# EasyEDAProDoc_P2303U1-electronicbox_2024.net
KiCad netlist of a schematic drawn in EasyEDA Pro
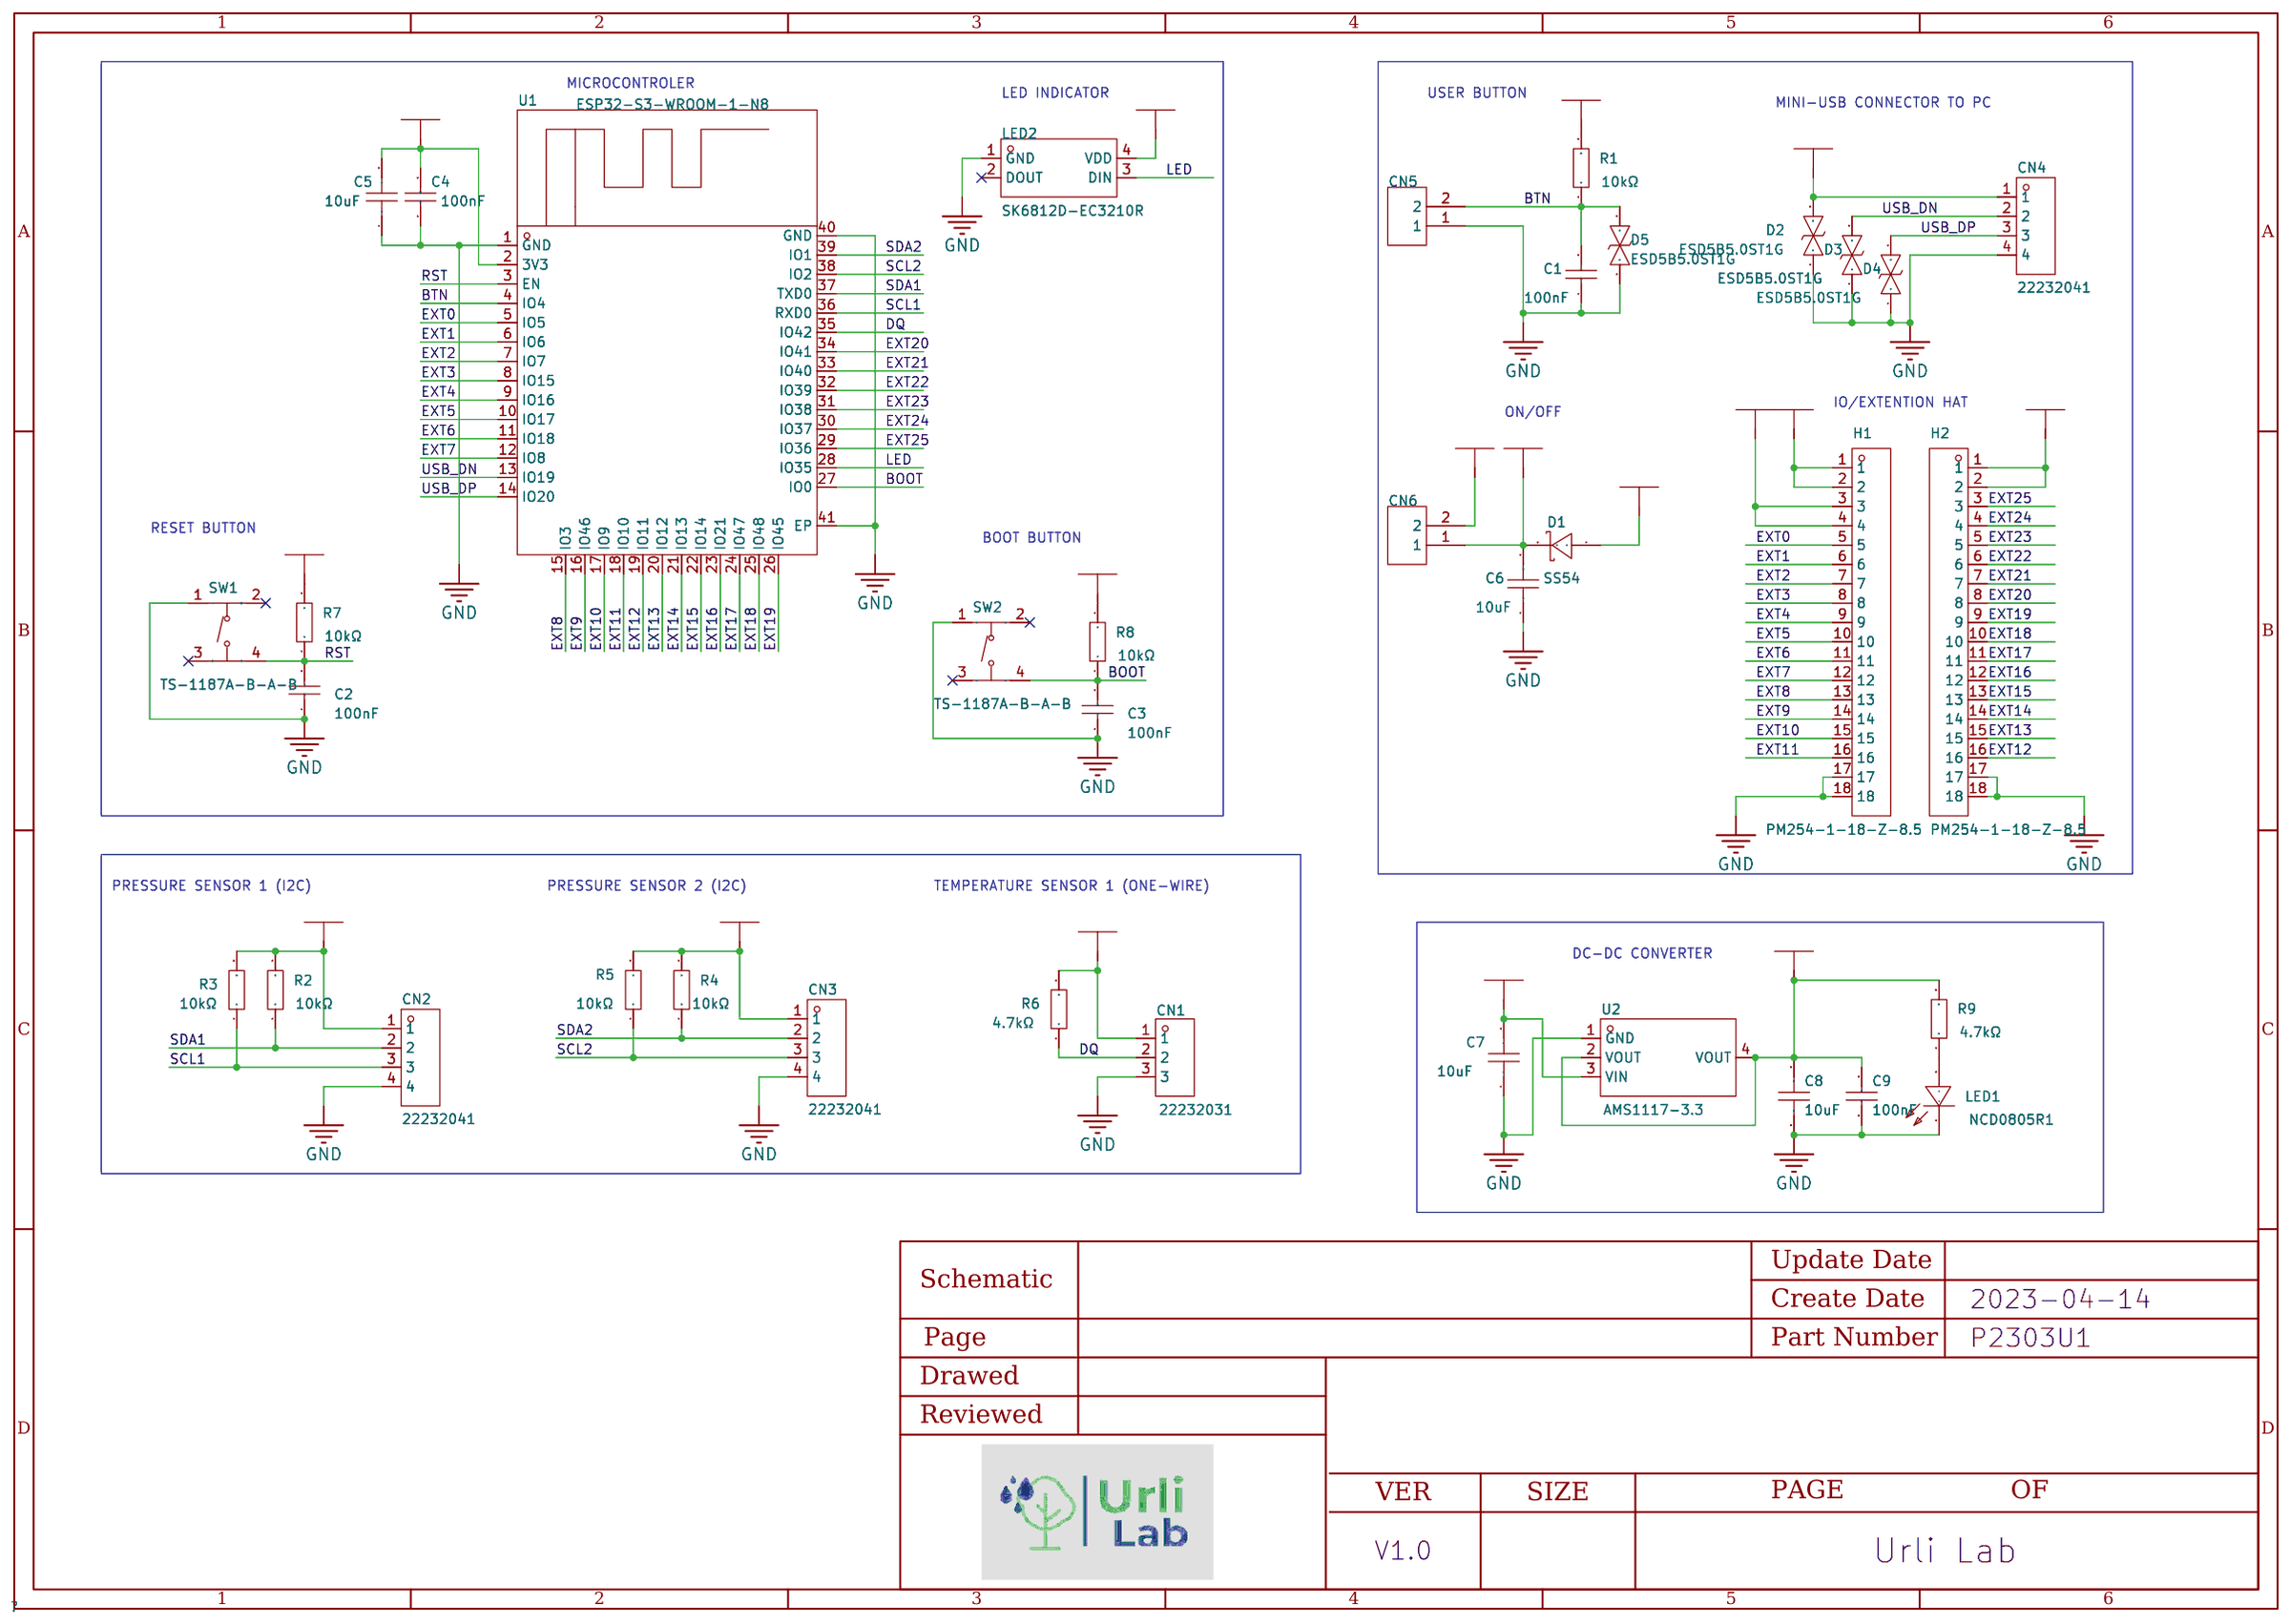
[diagram p0: schematic sheet]

(export (version "E")
  (design (tool "Eeschema 10.0.6"))
  (components
    (comp (ref "C1")
      (value "100nF")
      (footprint "easyedapro:C0805")
      (fields
        (field (name "Manufacturer Part") "CC0805KRX7R9BB104")
        (field (name "Manufacturer") "YAGEO(国巨)")
      )
      (libsource (lib "easyedapro") (part "CC0805KRX7R9BB104"))
    )
    (comp (ref "C2")
      (value "100nF")
      (footprint "easyedapro:C0805")
      (fields
        (field (name "Manufacturer Part") "CC0805KRX7R9BB104")
        (field (name "Manufacturer") "YAGEO(国巨)")
      )
      (libsource (lib "easyedapro") (part "CC0805KRX7R9BB104"))
    )
    (comp (ref "C3")
      (value "100nF")
      (footprint "easyedapro:C0805")
      (fields
        (field (name "Manufacturer Part") "CC0805KRX7R9BB104")
        (field (name "Manufacturer") "YAGEO(国巨)")
      )
      (libsource (lib "easyedapro") (part "CC0805KRX7R9BB104"))
    )
    (comp (ref "C4")
      (value "100nF")
      (footprint "easyedapro:C0805")
      (fields
        (field (name "Manufacturer Part") "CC0805KRX7R9BB104")
        (field (name "Manufacturer") "YAGEO(国巨)")
      )
      (libsource (lib "easyedapro") (part "CC0805KRX7R9BB104"))
    )
    (comp (ref "C5")
      (value "10uF")
      (footprint "easyedapro:C0805")
      (fields
        (field (name "Manufacturer Part") "GRM21BR61H106KE43L")
        (field (name "Manufacturer") "muRata(村田)")
      )
      (libsource (lib "easyedapro") (part "GRM21BR61H106KE43L"))
    )
    (comp (ref "C6")
      (value "10uF")
      (footprint "easyedapro:C0805")
      (fields
        (field (name "Manufacturer Part") "GRM21BR61H106KE43L")
        (field (name "Manufacturer") "muRata(村田)")
      )
      (libsource (lib "easyedapro") (part "GRM21BR61H106KE43L"))
    )
    (comp (ref "C7")
      (value "10uF")
      (footprint "easyedapro:C0805")
      (fields
        (field (name "Manufacturer Part") "GRM21BR61H106KE43L")
        (field (name "Manufacturer") "muRata(村田)")
      )
      (libsource (lib "easyedapro") (part "GRM21BR61H106KE43L"))
    )
    (comp (ref "C8")
      (value "10uF")
      (footprint "easyedapro:C0805")
      (fields
        (field (name "Manufacturer Part") "GRM21BR61H106KE43L")
        (field (name "Manufacturer") "muRata(村田)")
      )
      (libsource (lib "easyedapro") (part "GRM21BR61H106KE43L"))
    )
    (comp (ref "C9")
      (value "100nF")
      (footprint "easyedapro:C0805")
      (fields
        (field (name "Manufacturer Part") "CC0805KRX7R9BB104")
        (field (name "Manufacturer") "YAGEO(国巨)")
      )
      (libsource (lib "easyedapro") (part "CC0805KRX7R9BB104"))
    )
    (comp (ref "CN1")
      (value "22232031")
      (footprint "easyedapro:CONN-TH_3P-P2.54_22-23-2031")
      (fields (field (name "Manufacturer") "MOLEX"))
      (libsource (lib "easyedapro") (part "22-23-2031"))
    )
    (comp (ref "CN2")
      (value "22232041")
      (footprint "easyedapro:CONN-TH_4P-P2.54_22232041")
      (fields (field (name "Manufacturer") "MOLEX"))
      (libsource (lib "easyedapro") (part "22232041"))
    )
    (comp (ref "CN3")
      (value "22232041")
      (footprint "easyedapro:CONN-TH_4P-P2.54_22232041")
      (fields (field (name "Manufacturer") "MOLEX"))
      (libsource (lib "easyedapro") (part "22232041"))
    )
    (comp (ref "CN4")
      (value "22232041")
      (footprint "easyedapro:CONN-TH_4P-P2.54_22232041")
      (fields (field (name "Manufacturer") "MOLEX"))
      (libsource (lib "easyedapro") (part "22232041"))
    )
    (comp (ref "CN5")
      (value "22-23-2021")
      (fields (field (name "Manufacturer Part") "22232021") (field (name "Manufacturer") "MOLEX"))
      (libsource (lib "easyedapro") (part "0022232021"))
    )
    (comp (ref "CN6")
      (value "22-23-2021")
      (fields (field (name "Manufacturer Part") "22232021") (field (name "Manufacturer") "MOLEX"))
      (libsource (lib "easyedapro") (part "0022232021"))
    )
    (comp (ref "D1")
      (value "SS54")
      (footprint "easyedapro:SMA_L4.4-W2.8-LS5.4-R-RD")
      (description "Reverse Voltage (Vr):40V Average Rectified Current (Io):5A Forward Voltage (Vf@If):550mV@5A")
      (fields (field (name "Manufacturer") "MDD"))
      (libsource (lib "easyedapro") (part "SS54_C22452"))
    )
    (comp (ref "D2")
      (value "ESD5B5.0ST1G")
      (footprint "easyedapro:SOD-523_L1.2-W0.8-LS1.6-BI")
      (fields (field (name "Manufacturer") "onsemi(安森美)"))
      (libsource (lib "easyedapro") (part "ESD5B5.0ST1G"))
    )
    (comp (ref "D3")
      (value "ESD5B5.0ST1G")
      (footprint "easyedapro:SOD-523_L1.2-W0.8-LS1.6-BI")
      (fields (field (name "Manufacturer") "onsemi(安森美)"))
      (libsource (lib "easyedapro") (part "ESD5B5.0ST1G"))
    )
    (comp (ref "D4")
      (value "ESD5B5.0ST1G")
      (footprint "easyedapro:SOD-523_L1.2-W0.8-LS1.6-BI")
      (fields (field (name "Manufacturer") "onsemi(安森美)"))
      (libsource (lib "easyedapro") (part "ESD5B5.0ST1G"))
    )
    (comp (ref "D5")
      (value "ESD5B5.0ST1G")
      (footprint "easyedapro:SOD-523_L1.2-W0.8-LS1.6-BI")
      (fields (field (name "Manufacturer") "onsemi(安森美)"))
      (libsource (lib "easyedapro") (part "ESD5B5.0ST1G"))
    )
    (comp (ref "H1")
      (value "PM254-1-18-Z-8.5")
      (footprint "easyedapro:HDR-TH_18P-P2.54-V-F")
      (fields (field (name "Manufacturer") "HCTL(华灿天禄)"))
      (libsource (lib "easyedapro") (part "PM254-1-18-Z-8.5"))
    )
    (comp (ref "H2")
      (value "PM254-1-18-Z-8.5")
      (footprint "easyedapro:HDR-TH_18P-P2.54-V-F")
      (fields (field (name "Manufacturer") "HCTL(华灿天禄)"))
      (libsource (lib "easyedapro") (part "PM254-1-18-Z-8.5"))
    )
    (comp (ref "LED1")
      (value "NCD0805R1")
      (footprint "easyedapro:LED0805-RD_RED")
      (description "Emitted Color:红灯")
      (fields (field (name "Manufacturer") "国星光电"))
      (libsource (lib "easyedapro") (part "FC-2012HRK-620D"))
    )
    (comp (ref "LED2")
      (value "SK6812D-EC3210R")
      (footprint "easyedapro:LED-SMD_4P_SK6812D-EC3210R")
      (fields (field (name "Manufacturer") "欧思科光电"))
      (libsource (lib "easyedapro") (part "SK6812D-EC3210R"))
    )
    (comp (ref "R1")
      (value "10kΩ")
      (footprint "easyedapro:R0805")
      (fields
        (field (name "Manufacturer Part") "0805W8F1002T5E")
        (field (name "Manufacturer") "UNI-ROYAL(厚声)")
      )
      (libsource (lib "easyedapro") (part "0805W8F1002T5E"))
    )
    (comp (ref "R2")
      (value "10kΩ")
      (footprint "easyedapro:R0805")
      (fields
        (field (name "Manufacturer Part") "0805W8F1002T5E")
        (field (name "Manufacturer") "UNI-ROYAL(厚声)")
      )
      (libsource (lib "easyedapro") (part "0805W8F1002T5E"))
    )
    (comp (ref "R3")
      (value "10kΩ")
      (footprint "easyedapro:R0805")
      (fields
        (field (name "Manufacturer Part") "0805W8F1002T5E")
        (field (name "Manufacturer") "UNI-ROYAL(厚声)")
      )
      (libsource (lib "easyedapro") (part "0805W8F1002T5E"))
    )
    (comp (ref "R4")
      (value "10kΩ")
      (footprint "easyedapro:R0805")
      (fields
        (field (name "Manufacturer Part") "0805W8F1002T5E")
        (field (name "Manufacturer") "UNI-ROYAL(厚声)")
      )
      (libsource (lib "easyedapro") (part "0805W8F1002T5E"))
    )
    (comp (ref "R5")
      (value "10kΩ")
      (footprint "easyedapro:R0805")
      (fields
        (field (name "Manufacturer Part") "0805W8F1002T5E")
        (field (name "Manufacturer") "UNI-ROYAL(厚声)")
      )
      (libsource (lib "easyedapro") (part "0805W8F1002T5E"))
    )
    (comp (ref "R6")
      (value "4.7kΩ")
      (footprint "easyedapro:R0805")
      (fields
        (field (name "Manufacturer Part") "0805W8F4701T5E")
        (field (name "Manufacturer") "UNI-ROYAL(厚声)")
      )
      (libsource (lib "easyedapro") (part "0805W8F4701T5E"))
    )
    (comp (ref "R7")
      (value "10kΩ")
      (footprint "easyedapro:R0805")
      (fields
        (field (name "Manufacturer Part") "0805W8F1002T5E")
        (field (name "Manufacturer") "UNI-ROYAL(厚声)")
      )
      (libsource (lib "easyedapro") (part "0805W8F1002T5E"))
    )
    (comp (ref "R8")
      (value "10kΩ")
      (footprint "easyedapro:R0805")
      (fields
        (field (name "Manufacturer Part") "0805W8F1002T5E")
        (field (name "Manufacturer") "UNI-ROYAL(厚声)")
      )
      (libsource (lib "easyedapro") (part "0805W8F1002T5E"))
    )
    (comp (ref "R9")
      (value "4.7kΩ")
      (footprint "easyedapro:R0805")
      (fields
        (field (name "Manufacturer Part") "0805W8F4701T5E")
        (field (name "Manufacturer") "UNI-ROYAL(厚声)")
      )
      (libsource (lib "easyedapro") (part "0805W8F4701T5E"))
    )
    (comp (ref "SW1")
      (value "TS-1187A-B-A-B")
      (footprint "easyedapro:SW-SMD_4P-L5.1-W5.1-P3.70-LS6.5-TL-2")
      (fields (field (name "Manufacturer") "XKB Connectivity(中国星坤)"))
      (libsource (lib "easyedapro") (part "TS-1187A-B-A-B"))
    )
    (comp (ref "SW2")
      (value "TS-1187A-B-A-B")
      (footprint "easyedapro:SW-SMD_4P-L5.1-W5.1-P3.70-LS6.5-TL-2")
      (fields (field (name "Manufacturer") "XKB Connectivity(中国星坤)"))
      (libsource (lib "easyedapro") (part "TS-1187A-B-A-B"))
    )
    (comp (ref "U1")
      (value "ESP32-S3-WROOM-1-N8")
      (footprint "easyedapro:WIFIM-SMD_ESP32-S3-WROOM-1-N8")
      (fields (field (name "Manufacturer") "ESPRESSIF(乐鑫)"))
      (libsource (lib "easyedapro") (part "ESP32-S3-WROOM-1-N8"))
    )
    (comp (ref "U2")
      (value "AMS1117-3.3")
      (footprint "easyedapro:SOT-223-3_L6.5-W3.4-P2.30-LS7.0-BR")
      (fields (field (name "Manufacturer") "AMS"))
      (libsource (lib "easyedapro") (part "AMS1117-3.3"))
    )
  )
  (nets
    (net (code "1") (name "/BOOT") (class "Default")
      (node (ref "C3") (pin "2") (pinfunction "2_2") (pintype "input"))
      (node (ref "R8") (pin "1") (pinfunction "1_1") (pintype "input"))
      (node (ref "SW2") (pin "4") (pinfunction "D_4") (pintype "input"))
      (node (ref "U1") (pin "27") (pinfunction "IO0_27") (pintype "input"))
    )
    (net (code "2") (name "/BTN") (class "Default")
      (node (ref "C1") (pin "2") (pinfunction "2_2") (pintype "input"))
      (node (ref "CN5") (pin "2") (pinfunction "2_2") (pintype "input"))
      (node (ref "D5") (pin "2") (pinfunction "2_2") (pintype "input"))
      (node (ref "R1") (pin "1") (pinfunction "1_1") (pintype "input"))
      (node (ref "U1") (pin "4") (pinfunction "IO4_4") (pintype "input"))
    )
    (net (code "3") (name "/DQ") (class "Default")
      (node (ref "CN1") (pin "2") (pinfunction "2_2") (pintype "input"))
      (node (ref "R6") (pin "1") (pinfunction "1_1") (pintype "input"))
      (node (ref "U1") (pin "35") (pinfunction "IO42_35") (pintype "input"))
    )
    (net (code "4") (name "/EXT0") (class "Default")
      (node (ref "H1") (pin "5") (pinfunction "5_5") (pintype "input"))
      (node (ref "U1") (pin "5") (pinfunction "IO5_5") (pintype "input"))
    )
    (net (code "5") (name "/EXT1") (class "Default")
      (node (ref "H1") (pin "6") (pinfunction "6_6") (pintype "input"))
      (node (ref "U1") (pin "6") (pinfunction "IO6_6") (pintype "input"))
    )
    (net (code "6") (name "/EXT2") (class "Default")
      (node (ref "H1") (pin "7") (pinfunction "7_7") (pintype "input"))
      (node (ref "U1") (pin "7") (pinfunction "IO7_7") (pintype "input"))
    )
    (net (code "7") (name "/EXT3") (class "Default")
      (node (ref "H1") (pin "8") (pinfunction "8_8") (pintype "input"))
      (node (ref "U1") (pin "8") (pinfunction "IO15_8") (pintype "input"))
    )
    (net (code "8") (name "/EXT4") (class "Default")
      (node (ref "H1") (pin "9") (pinfunction "9_9") (pintype "input"))
      (node (ref "U1") (pin "9") (pinfunction "IO16_9") (pintype "input"))
    )
    (net (code "9") (name "/EXT5") (class "Default")
      (node (ref "H1") (pin "10") (pinfunction "10_10") (pintype "input"))
      (node (ref "U1") (pin "10") (pinfunction "IO17_10") (pintype "input"))
    )
    (net (code "10") (name "/EXT6") (class "Default")
      (node (ref "H1") (pin "11") (pinfunction "11_11") (pintype "input"))
      (node (ref "U1") (pin "11") (pinfunction "IO18_11") (pintype "input"))
    )
    (net (code "11") (name "/EXT7") (class "Default")
      (node (ref "H1") (pin "12") (pinfunction "12_12") (pintype "input"))
      (node (ref "U1") (pin "12") (pinfunction "IO8_12") (pintype "input"))
    )
    (net (code "12") (name "/EXT8") (class "Default")
      (node (ref "H1") (pin "13") (pinfunction "13_13") (pintype "input"))
      (node (ref "U1") (pin "15") (pinfunction "IO3_15") (pintype "input"))
    )
    (net (code "13") (name "/EXT9") (class "Default")
      (node (ref "H1") (pin "14") (pinfunction "14_14") (pintype "input"))
      (node (ref "U1") (pin "16") (pinfunction "IO46_16") (pintype "input"))
    )
    (net (code "14") (name "/EXT10") (class "Default")
      (node (ref "H1") (pin "15") (pinfunction "15_15") (pintype "input"))
      (node (ref "U1") (pin "17") (pinfunction "IO9_17") (pintype "input"))
    )
    (net (code "15") (name "/EXT11") (class "Default")
      (node (ref "H1") (pin "16") (pinfunction "16_16") (pintype "input"))
      (node (ref "U1") (pin "18") (pinfunction "IO10_18") (pintype "input"))
    )
    (net (code "16") (name "/EXT12") (class "Default")
      (node (ref "H2") (pin "16") (pinfunction "16_16") (pintype "input"))
      (node (ref "U1") (pin "19") (pinfunction "IO11_19") (pintype "input"))
    )
    (net (code "17") (name "/EXT13") (class "Default")
      (node (ref "H2") (pin "15") (pinfunction "15_15") (pintype "input"))
      (node (ref "U1") (pin "20") (pinfunction "IO12_20") (pintype "input"))
    )
    (net (code "18") (name "/EXT14") (class "Default")
      (node (ref "H2") (pin "14") (pinfunction "14_14") (pintype "input"))
      (node (ref "U1") (pin "21") (pinfunction "IO13_21") (pintype "input"))
    )
    (net (code "19") (name "/EXT15") (class "Default")
      (node (ref "H2") (pin "13") (pinfunction "13_13") (pintype "input"))
      (node (ref "U1") (pin "22") (pinfunction "IO14_22") (pintype "input"))
    )
    (net (code "20") (name "/EXT16") (class "Default")
      (node (ref "H2") (pin "12") (pinfunction "12_12") (pintype "input"))
      (node (ref "U1") (pin "23") (pinfunction "IO21_23") (pintype "input"))
    )
    (net (code "21") (name "/EXT17") (class "Default")
      (node (ref "H2") (pin "11") (pinfunction "11_11") (pintype "input"))
      (node (ref "U1") (pin "24") (pinfunction "IO47_24") (pintype "input"))
    )
    (net (code "22") (name "/EXT18") (class "Default")
      (node (ref "H2") (pin "10") (pinfunction "10_10") (pintype "input"))
      (node (ref "U1") (pin "25") (pinfunction "IO48_25") (pintype "input"))
    )
    (net (code "23") (name "/EXT19") (class "Default")
      (node (ref "H2") (pin "9") (pinfunction "9_9") (pintype "input"))
      (node (ref "U1") (pin "26") (pinfunction "IO45_26") (pintype "input"))
    )
    (net (code "24") (name "/EXT20") (class "Default")
      (node (ref "H2") (pin "8") (pinfunction "8_8") (pintype "input"))
      (node (ref "U1") (pin "34") (pinfunction "IO41_34") (pintype "input"))
    )
    (net (code "25") (name "/EXT21") (class "Default")
      (node (ref "H2") (pin "7") (pinfunction "7_7") (pintype "input"))
      (node (ref "U1") (pin "33") (pinfunction "IO40_33") (pintype "input"))
    )
    (net (code "26") (name "/EXT22") (class "Default")
      (node (ref "H2") (pin "6") (pinfunction "6_6") (pintype "input"))
      (node (ref "U1") (pin "32") (pinfunction "IO39_32") (pintype "input"))
    )
    (net (code "27") (name "/EXT23") (class "Default")
      (node (ref "H2") (pin "5") (pinfunction "5_5") (pintype "input"))
      (node (ref "U1") (pin "31") (pinfunction "IO38_31") (pintype "input"))
    )
    (net (code "28") (name "/EXT24") (class "Default")
      (node (ref "H2") (pin "4") (pinfunction "4_4") (pintype "input"))
      (node (ref "U1") (pin "30") (pinfunction "IO37_30") (pintype "input"))
    )
    (net (code "29") (name "/EXT25") (class "Default")
      (node (ref "H2") (pin "3") (pinfunction "3_3") (pintype "input"))
      (node (ref "U1") (pin "29") (pinfunction "IO36_29") (pintype "input"))
    )
    (net (code "30") (name "/LED") (class "Default")
      (node (ref "LED2") (pin "3") (pinfunction "DIN_3") (pintype "input"))
      (node (ref "U1") (pin "28") (pinfunction "IO35_28") (pintype "input"))
    )
    (net (code "31") (name "/RST") (class "Default")
      (node (ref "C2") (pin "2") (pinfunction "2_2") (pintype "input"))
      (node (ref "R7") (pin "1") (pinfunction "1_1") (pintype "input"))
      (node (ref "SW1") (pin "4") (pinfunction "D_4") (pintype "input"))
      (node (ref "U1") (pin "3") (pinfunction "EN_3") (pintype "input"))
    )
    (net (code "32") (name "/SCL1") (class "Default")
      (node (ref "CN2") (pin "3") (pinfunction "3_3") (pintype "input"))
      (node (ref "R3") (pin "1") (pinfunction "1_1") (pintype "input"))
      (node (ref "U1") (pin "36") (pinfunction "RXD0_36") (pintype "input"))
    )
    (net (code "33") (name "/SCL2") (class "Default")
      (node (ref "CN3") (pin "3") (pinfunction "3_3") (pintype "input"))
      (node (ref "R5") (pin "1") (pinfunction "1_1") (pintype "input"))
      (node (ref "U1") (pin "38") (pinfunction "IO2_38") (pintype "input"))
    )
    (net (code "34") (name "/SDA1") (class "Default")
      (node (ref "CN2") (pin "2") (pinfunction "2_2") (pintype "input"))
      (node (ref "R2") (pin "1") (pinfunction "1_1") (pintype "input"))
      (node (ref "U1") (pin "37") (pinfunction "TXD0_37") (pintype "input"))
    )
    (net (code "35") (name "/SDA2") (class "Default")
      (node (ref "CN3") (pin "2") (pinfunction "2_2") (pintype "input"))
      (node (ref "R4") (pin "1") (pinfunction "1_1") (pintype "input"))
      (node (ref "U1") (pin "39") (pinfunction "IO1_39") (pintype "input"))
    )
    (net (code "36") (name "/USB_DN") (class "Default")
      (node (ref "CN4") (pin "2") (pinfunction "2_2") (pintype "input"))
      (node (ref "D3") (pin "2") (pinfunction "2_2") (pintype "input"))
      (node (ref "U1") (pin "13") (pinfunction "IO19_13") (pintype "input"))
    )
    (net (code "37") (name "/USB_DP") (class "Default")
      (node (ref "CN4") (pin "3") (pinfunction "3_3") (pintype "input"))
      (node (ref "D4") (pin "2") (pinfunction "2_2") (pintype "input"))
      (node (ref "U1") (pin "14") (pinfunction "IO20_14") (pintype "input"))
    )
    (net (code "38") (name "3V3") (class "Default")
      (node (ref "C4") (pin "2") (pinfunction "2_2") (pintype "input"))
      (node (ref "C5") (pin "2") (pinfunction "2_2") (pintype "input"))
      (node (ref "C8") (pin "2") (pinfunction "2_2") (pintype "input"))
      (node (ref "C9") (pin "2") (pinfunction "2_2") (pintype "input"))
      (node (ref "CN1") (pin "1") (pinfunction "1_1") (pintype "input"))
      (node (ref "CN2") (pin "1") (pinfunction "1_1") (pintype "input"))
      (node (ref "CN3") (pin "1") (pinfunction "1_1") (pintype "input"))
      (node (ref "H2") (pin "1") (pinfunction "1_1") (pintype "input"))
      (node (ref "H2") (pin "2") (pinfunction "2_2") (pintype "input"))
      (node (ref "LED2") (pin "4") (pinfunction "VDD_4") (pintype "input"))
      (node (ref "R1") (pin "2") (pinfunction "2_2") (pintype "input"))
      (node (ref "R2") (pin "2") (pinfunction "2_2") (pintype "input"))
      (node (ref "R3") (pin "2") (pinfunction "2_2") (pintype "input"))
      (node (ref "R4") (pin "2") (pinfunction "2_2") (pintype "input"))
      (node (ref "R5") (pin "2") (pinfunction "2_2") (pintype "input"))
      (node (ref "R6") (pin "2") (pinfunction "2_2") (pintype "input"))
      (node (ref "R7") (pin "2") (pinfunction "2_2") (pintype "input"))
      (node (ref "R8") (pin "2") (pinfunction "2_2") (pintype "input"))
      (node (ref "R9") (pin "2") (pinfunction "2_2") (pintype "input"))
      (node (ref "U1") (pin "2") (pinfunction "3V3_2") (pintype "input"))
      (node (ref "U2") (pin "2") (pinfunction "VOUT_2") (pintype "input"))
      (node (ref "U2") (pin "4") (pinfunction "VOUT_4") (pintype "input"))
    )
    (net (code "39") (name "GND") (class "Default")
      (node (ref "C1") (pin "1") (pinfunction "1_1") (pintype "input"))
      (node (ref "C2") (pin "1") (pinfunction "1_1") (pintype "input"))
      (node (ref "C3") (pin "1") (pinfunction "1_1") (pintype "input"))
      (node (ref "C4") (pin "1") (pinfunction "1_1") (pintype "input"))
      (node (ref "C5") (pin "1") (pinfunction "1_1") (pintype "input"))
      (node (ref "C6") (pin "1") (pinfunction "1_1") (pintype "input"))
      (node (ref "C7") (pin "1") (pinfunction "1_1") (pintype "input"))
      (node (ref "C8") (pin "1") (pinfunction "1_1") (pintype "input"))
      (node (ref "C9") (pin "1") (pinfunction "1_1") (pintype "input"))
      (node (ref "CN1") (pin "3") (pinfunction "3_3") (pintype "input"))
      (node (ref "CN2") (pin "4") (pinfunction "4_4") (pintype "input"))
      (node (ref "CN3") (pin "4") (pinfunction "4_4") (pintype "input"))
      (node (ref "CN4") (pin "4") (pinfunction "4_4") (pintype "input"))
      (node (ref "CN5") (pin "1") (pinfunction "1_1") (pintype "input"))
      (node (ref "D2") (pin "1") (pinfunction "1_1") (pintype "input"))
      (node (ref "D3") (pin "1") (pinfunction "1_1") (pintype "input"))
      (node (ref "D4") (pin "1") (pinfunction "1_1") (pintype "input"))
      (node (ref "D5") (pin "1") (pinfunction "1_1") (pintype "input"))
      (node (ref "H1") (pin "17") (pinfunction "17_17") (pintype "input"))
      (node (ref "H1") (pin "18") (pinfunction "18_18") (pintype "input"))
      (node (ref "H2") (pin "17") (pinfunction "17_17") (pintype "input"))
      (node (ref "H2") (pin "18") (pinfunction "18_18") (pintype "input"))
      (node (ref "LED1") (pin "1") (pinfunction "-_1") (pintype "input"))
      (node (ref "LED2") (pin "1") (pinfunction "GND_1") (pintype "input"))
      (node (ref "SW1") (pin "1") (pinfunction "A_1") (pintype "input"))
      (node (ref "SW2") (pin "1") (pinfunction "A_1") (pintype "input"))
      (node (ref "U1") (pin "1") (pinfunction "GND_1") (pintype "input"))
      (node (ref "U1") (pin "40") (pinfunction "GND_40") (pintype "input"))
      (node (ref "U1") (pin "41") (pinfunction "EP_41") (pintype "input"))
      (node (ref "U2") (pin "1") (pinfunction "GND_1") (pintype "input"))
    )
    (net (code "40") (name "Net-(LED1-+)") (class "Default")
      (node (ref "LED1") (pin "2") (pinfunction "+_2") (pintype "input"))
      (node (ref "R9") (pin "1") (pinfunction "1_1") (pintype "input"))
    )
    (net (code "41") (name "VBUS") (class "Default")
      (node (ref "CN4") (pin "1") (pinfunction "1_1") (pintype "input"))
      (node (ref "D1") (pin "1") (pinfunction "A_1") (pintype "input"))
      (node (ref "D2") (pin "2") (pinfunction "2_2") (pintype "input"))
    )
    (net (code "42") (name "VCC") (class "Default")
      (node (ref "C7") (pin "2") (pinfunction "2_2") (pintype "input"))
      (node (ref "CN6") (pin "2") (pinfunction "2_2") (pintype "input"))
      (node (ref "H1") (pin "1") (pinfunction "1_1") (pintype "input"))
      (node (ref "H1") (pin "2") (pinfunction "2_2") (pintype "input"))
      (node (ref "U2") (pin "3") (pinfunction "VIN_3") (pintype "input"))
    )
    (net (code "43") (name "VIN") (class "Default")
      (node (ref "C6") (pin "2") (pinfunction "2_2") (pintype "input"))
      (node (ref "CN6") (pin "1") (pinfunction "1_1") (pintype "input"))
      (node (ref "D1") (pin "2") (pinfunction "K_2") (pintype "input"))
      (node (ref "H1") (pin "3") (pinfunction "3_3") (pintype "input"))
      (node (ref "H1") (pin "4") (pinfunction "4_4") (pintype "input"))
    )
    (net (code "44") (name "unconnected-(LED2-DOUT-Pad2)") (class "Default")
      (node (ref "LED2") (pin "2") (pinfunction "DOUT_2") (pintype "input+no_connect"))
    )
    (net (code "45") (name "unconnected-(SW1-B-Pad2)") (class "Default")
      (node (ref "SW1") (pin "2") (pinfunction "B_2") (pintype "input+no_connect"))
    )
    (net (code "46") (name "unconnected-(SW1-C-Pad3)") (class "Default")
      (node (ref "SW1") (pin "3") (pinfunction "C_3") (pintype "input+no_connect"))
    )
    (net (code "47") (name "unconnected-(SW2-B-Pad2)") (class "Default")
      (node (ref "SW2") (pin "2") (pinfunction "B_2") (pintype "input+no_connect"))
    )
    (net (code "48") (name "unconnected-(SW2-C-Pad3)") (class "Default")
      (node (ref "SW2") (pin "3") (pinfunction "C_3") (pintype "input+no_connect"))
    )
  )
)
